# LO_synth_sma.net
KiCad netlist of a schematic drawn in EAGLE
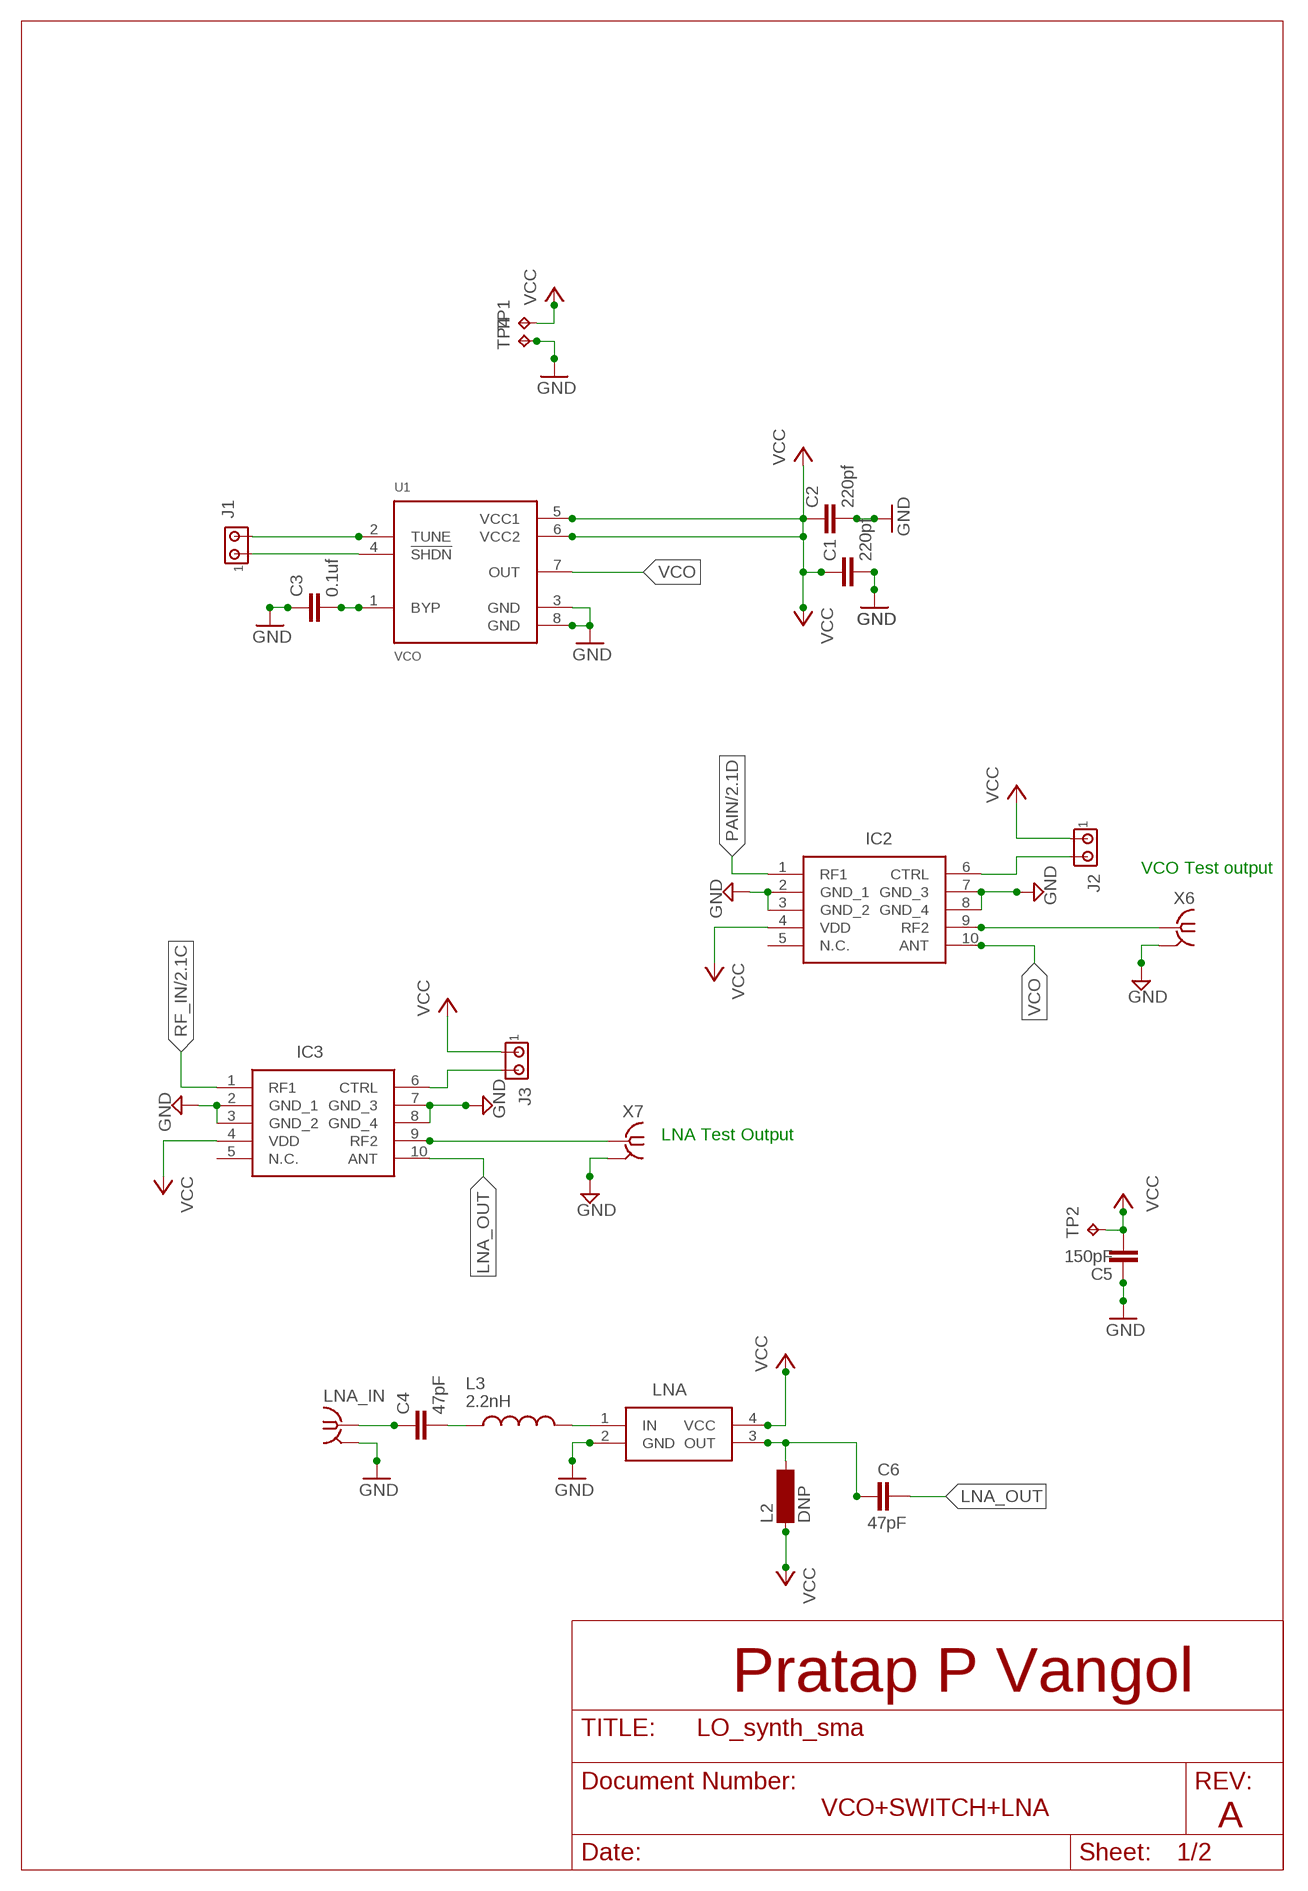
[diagram p0: schematic, sheet 1]
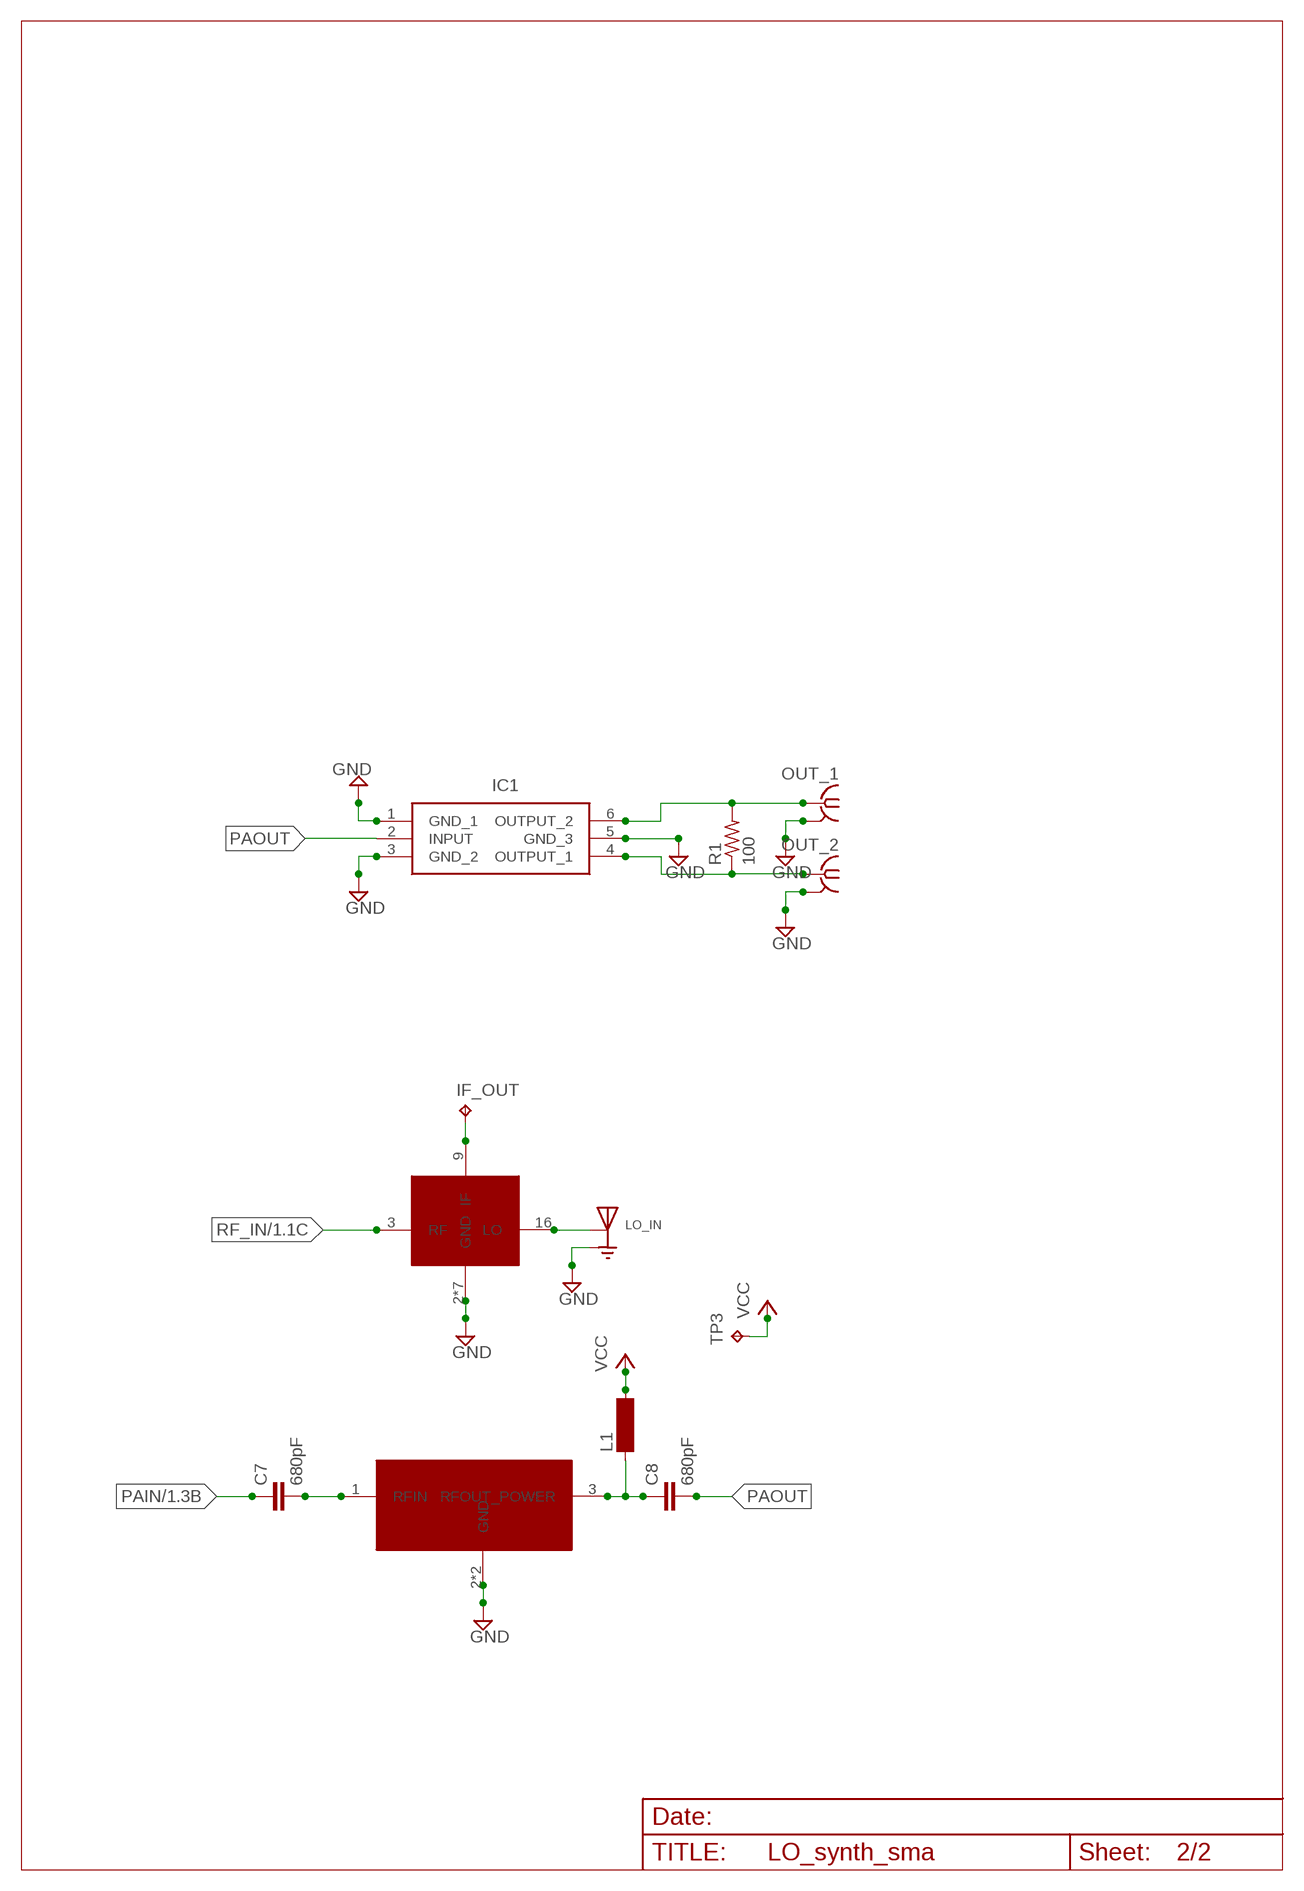
[diagram p1: schematic, sheet 2]

(export (version "E")
  (design (tool "Eeschema 10.0.6"))
  (components
    (comp (ref "C1")
      (value "220pf")
      (footprint "eagle-import:C0805")
      (libsource (lib "eagle-import") (part "C-EUC0805"))
    )
    (comp (ref "C2")
      (value "220pf")
      (footprint "eagle-import:C0805")
      (libsource (lib "eagle-import") (part "C-EUC0805"))
    )
    (comp (ref "C3")
      (value "0.1uf")
      (footprint "eagle-import:C0805")
      (libsource (lib "eagle-import") (part "C-EUC0805"))
    )
    (comp (ref "C4")
      (value "47pF")
      (footprint "eagle-import:C0805K")
      (libsource (lib "eagle-import") (part "C-EUC0805K"))
    )
    (comp (ref "C5")
      (value "150pF")
      (footprint "eagle-import:C0805K")
      (libsource (lib "eagle-import") (part "C-EUC0805K"))
    )
    (comp (ref "C6")
      (value "47pF")
      (footprint "eagle-import:C0805K")
      (libsource (lib "eagle-import") (part "C-EUC0805K"))
    )
    (comp (ref "IC2")
      (value "BGS12PN10E6327XTSA1")
      (footprint "eagle-import:BGSA11GN10E6327XTSA1")
      (fields (field (name "MOUSER_PART_NUMBER") "726-BGS12PN10E6327XT"))
      (libsource (lib "eagle-import") (part "BGS12PN10E6327XTSA1"))
    )
    (comp (ref "IC3")
      (value "BGS12PN10E6327XTSA1")
      (footprint "eagle-import:BGSA11GN10E6327XTSA1")
      (fields (field (name "MOUSER_PART_NUMBER") "726-BGS12PN10E6327XT"))
      (libsource (lib "eagle-import") (part "BGS12PN10E6327XTSA1"))
    )
    (comp (ref "J1")
      (value "MTA02-100")
      (footprint "eagle-import:10X02MTA")
      (libsource (lib "eagle-import") (part "MTA02-100"))
    )
    (comp (ref "J2")
      (value "MTA02-100")
      (footprint "eagle-import:10X02MTA")
      (fields (field (name "SPICEPREFIX") "B"))
      (libsource (lib "eagle-import") (part "MTA02-100"))
    )
    (comp (ref "J3")
      (value "MTA02-100")
      (footprint "eagle-import:10X02MTA")
      (fields (field (name "SPICEPREFIX") "B"))
      (libsource (lib "eagle-import") (part "MTA02-100"))
    )
    (comp (ref "L2")
      (value "DNP")
      (footprint "eagle-import:MS85")
      (libsource (lib "eagle-import") (part "MS85"))
    )
    (comp (ref "L3")
      (value "2.2nH")
      (footprint "eagle-import:INDC2012X103N")
      (fields (field (name "MF") "Bourns") (field (name "MP") "CE201210-2N2D"))
      (libsource (lib "eagle-import") (part "CE201210-2N2D"))
    )
    (comp (ref "LNA")
      (value "BGA622H6820XTSA1")
      (footprint "eagle-import:BGA622H6820XTSA1")
      (fields (field (name "MOUSER_PART_NUMBER") "726-BGA622H6820XTSA1"))
      (libsource (lib "eagle-import") (part "BGA622H6820XTSA1"))
    )
    (comp (ref "LNA_IN")
      (value "SMA-142-0711-821/826")
      (footprint "eagle-import:J502-ND-142-0711-821_826")
      (fields (field (name "MF") "JOHNSON COMPONENTS") (field (name "MPN") "142-0711-821"))
      (libsource (lib "eagle-import") (part "SMA-142-0711-821/826"))
    )
    (comp (ref "TP1")
      (value "TPPAD1-13")
      (footprint "eagle-import:P1-13")
      (libsource (lib "eagle-import") (part "TPPAD1-13"))
    )
    (comp (ref "TP2")
      (value "TPPAD1-13")
      (footprint "eagle-import:P1-13")
      (libsource (lib "eagle-import") (part "TPPAD1-13"))
    )
    (comp (ref "TP4")
      (value "TPPAD1-13")
      (footprint "eagle-import:P1-13")
      (libsource (lib "eagle-import") (part "TPPAD1-13"))
    )
    (comp (ref "U1")
      (value "VCO")
      (footprint "eagle-import:SOP65P490X110-8N")
      (fields (field (name "MF") "Maxim Integrated") (field (name "MP") "MAX2750EUA+"))
      (libsource (lib "eagle-import") (part "MAX2750EUA+"))
    )
    (comp (ref "X6")
      (value "VCO Test")
      (footprint "eagle-import:J502-ND-142-0711-821_826")
      (fields (field (name "MF") "JOHNSON COMPONENTS") (field (name "MPN") "142-0711-821"))
      (libsource (lib "eagle-import") (part "SMA-142-0711-821/826"))
    )
    (comp (ref "X7")
      (value "SMA-142-0711-821/826")
      (footprint "eagle-import:J502-ND-142-0711-821_826")
      (fields (field (name "MF") "JOHNSON COMPONENTS") (field (name "MPN") "142-0711-821"))
      (libsource (lib "eagle-import") (part "SMA-142-0711-821/826"))
    )
    (comp (ref "C7")
      (value "680pF")
      (footprint "eagle-import:C0805K")
      (libsource (lib "eagle-import") (part "C-EUC0805K"))
    )
    (comp (ref "C8")
      (value "680pF")
      (footprint "eagle-import:C0805K")
      (libsource (lib "eagle-import") (part "C-EUC0805K"))
    )
    (comp (ref "IC1")
      (value "PD2425J5050S2HF")
      (footprint "eagle-import:PD2425J5050S2HF")
      (fields (field (name "MOUSER_PART_NUMBER") "620-PD2425J5050S2HF"))
      (libsource (lib "eagle-import") (part "PD2425J5050S2HF"))
    )
    (comp (ref "IF_OUT")
      (value "TPPAD1-13")
      (footprint "eagle-import:P1-13")
      (libsource (lib "eagle-import") (part "TPPAD1-13"))
    )
    (comp (ref "L1")
      (value "MS85")
      (footprint "eagle-import:MS85")
      (libsource (lib "eagle-import") (part "MS85"))
    )
    (comp (ref "LO_IN")
      (value "U.FL-R-SMT-1(10)")
      (footprint "eagle-import:HRS_U.FL-R-SMT-1(10)")
      (fields (field (name "MF") "Hirose") (field (name "MP") "U.FL-R-SMT-1_10_"))
      (libsource (lib "eagle-import") (part "U.FL-R-SMT-1(10)"))
    )
    (comp (ref "OUT_1")
      (value "SMA-142-0711-821/826")
      (footprint "eagle-import:J502-ND-142-0711-821_826")
      (fields (field (name "MF") "JOHNSON COMPONENTS") (field (name "MPN") "142-0711-821"))
      (libsource (lib "eagle-import") (part "SMA-142-0711-821/826"))
    )
    (comp (ref "OUT_2")
      (value "SMA-142-0711-821/826")
      (footprint "eagle-import:J502-ND-142-0711-821_826")
      (fields (field (name "MF") "JOHNSON COMPONENTS") (field (name "MPN") "142-0711-821"))
      (libsource (lib "eagle-import") (part "SMA-142-0711-821/826"))
    )
    (comp (ref "R1")
      (value "100")
      (footprint "eagle-import:R0603")
      (libsource (lib "eagle-import") (part "R-US_R0603"))
    )
    (comp (ref "TP3")
      (value "TPPAD1-13")
      (footprint "eagle-import:P1-13")
      (libsource (lib "eagle-import") (part "TPPAD1-13"))
    )
    (comp (ref "U$1")
      (value "MDB-73H+QFN-24")
      (footprint "eagle-import:QFN24")
      (libsource (lib "eagle-import") (part "MDB-73H+QFN-24"))
    )
    (comp (ref "U$2")
      (value "GVA-60+")
      (footprint "eagle-import:SOT89")
      (libsource (lib "eagle-import") (part "GVA-60+"))
    )
  )
  (nets
    (net (code "1") (name "GND") (class "Default")
      (node (ref "C1") (pin "2") (pinfunction "2_2") (pintype "passive"))
      (node (ref "C2") (pin "2") (pinfunction "2_2") (pintype "passive"))
      (node (ref "C3") (pin "1") (pinfunction "1_1") (pintype "passive"))
      (node (ref "C5") (pin "1") (pinfunction "1_1") (pintype "passive"))
      (node (ref "IC1") (pin "1") (pinfunction "GND_1_1") (pintype "bidirectional"))
      (node (ref "IC1") (pin "3") (pinfunction "GND_2_3") (pintype "bidirectional"))
      (node (ref "IC1") (pin "5") (pinfunction "GND_3_5") (pintype "bidirectional"))
      (node (ref "IC2") (pin "2") (pinfunction "GND_1_2") (pintype "bidirectional"))
      (node (ref "IC2") (pin "3") (pinfunction "GND_2_3") (pintype "bidirectional"))
      (node (ref "IC2") (pin "7") (pinfunction "GND_3_7") (pintype "bidirectional"))
      (node (ref "IC2") (pin "8") (pinfunction "GND_4_8") (pintype "bidirectional"))
      (node (ref "IC3") (pin "2") (pinfunction "GND_1_2") (pintype "bidirectional"))
      (node (ref "IC3") (pin "3") (pinfunction "GND_2_3") (pintype "bidirectional"))
      (node (ref "IC3") (pin "7") (pinfunction "GND_3_7") (pintype "bidirectional"))
      (node (ref "IC3") (pin "8") (pinfunction "GND_4_8") (pintype "bidirectional"))
      (node (ref "LNA") (pin "2") (pinfunction "GND_2") (pintype "bidirectional"))
      (node (ref "LNA_IN") (pin "G@1") (pinfunction "2_G@1") (pintype "passive"))
      (node (ref "LNA_IN") (pin "G@2") (pinfunction "2_G@2") (pintype "passive"))
      (node (ref "LNA_IN") (pin "G@3") (pinfunction "2_G@3") (pintype "passive"))
      (node (ref "LNA_IN") (pin "G@4") (pinfunction "2_G@4") (pintype "passive"))
      (node (ref "LO_IN") (pin "1") (pinfunction "GND_1") (pintype "passive"))
      (node (ref "LO_IN") (pin "3") (pinfunction "GND_3") (pintype "passive"))
      (node (ref "OUT_1") (pin "G@1") (pinfunction "2_G@1") (pintype "passive"))
      (node (ref "OUT_1") (pin "G@2") (pinfunction "2_G@2") (pintype "passive"))
      (node (ref "OUT_1") (pin "G@3") (pinfunction "2_G@3") (pintype "passive"))
      (node (ref "OUT_1") (pin "G@4") (pinfunction "2_G@4") (pintype "passive"))
      (node (ref "OUT_2") (pin "G@1") (pinfunction "2_G@1") (pintype "passive"))
      (node (ref "OUT_2") (pin "G@2") (pinfunction "2_G@2") (pintype "passive"))
      (node (ref "OUT_2") (pin "G@3") (pinfunction "2_G@3") (pintype "passive"))
      (node (ref "OUT_2") (pin "G@4") (pinfunction "2_G@4") (pintype "passive"))
      (node (ref "TP4") (pin "TP") (pinfunction "TP_TP") (pintype "input"))
      (node (ref "U$1") (pin "10") (pinfunction "GND_10") (pintype "bidirectional"))
      (node (ref "U$1") (pin "15") (pinfunction "GND_15") (pintype "bidirectional"))
      (node (ref "U$1") (pin "17") (pinfunction "GND_17") (pintype "bidirectional"))
      (node (ref "U$1") (pin "2") (pinfunction "GND_2") (pintype "bidirectional"))
      (node (ref "U$1") (pin "4") (pinfunction "GND_4") (pintype "bidirectional"))
      (node (ref "U$1") (pin "8") (pinfunction "GND_8") (pintype "bidirectional"))
      (node (ref "U$1") (pin "PD") (pinfunction "GND_PD") (pintype "bidirectional"))
      (node (ref "U$2") (pin "2") (pinfunction "GND_2") (pintype "power_in"))
      (node (ref "U$2") (pin "2@1") (pinfunction "GND_2@1") (pintype "power_in"))
      (node (ref "U1") (pin "3") (pinfunction "GND_3") (pintype "power_in"))
      (node (ref "U1") (pin "8") (pinfunction "GND_8") (pintype "power_in"))
      (node (ref "X6") (pin "G@1") (pinfunction "2_G@1") (pintype "passive"))
      (node (ref "X6") (pin "G@2") (pinfunction "2_G@2") (pintype "passive"))
      (node (ref "X6") (pin "G@3") (pinfunction "2_G@3") (pintype "passive"))
      (node (ref "X6") (pin "G@4") (pinfunction "2_G@4") (pintype "passive"))
      (node (ref "X7") (pin "G@1") (pinfunction "2_G@1") (pintype "passive"))
      (node (ref "X7") (pin "G@2") (pinfunction "2_G@2") (pintype "passive"))
      (node (ref "X7") (pin "G@3") (pinfunction "2_G@3") (pintype "passive"))
      (node (ref "X7") (pin "G@4") (pinfunction "2_G@4") (pintype "passive"))
    )
    (net (code "2") (name "LNA_OUT") (class "Default")
      (node (ref "C6") (pin "2") (pinfunction "2_2") (pintype "passive"))
      (node (ref "IC3") (pin "10") (pinfunction "ANT_10") (pintype "bidirectional"))
    )
    (net (code "3") (name "Net-(C4-Pad1)") (class "Default")
      (node (ref "C4") (pin "1") (pinfunction "1_1") (pintype "passive"))
      (node (ref "LNA_IN") (pin "1") (pinfunction "1_1") (pintype "passive"))
    )
    (net (code "4") (name "Net-(C4-Pad2)") (class "Default")
      (node (ref "C4") (pin "2") (pinfunction "2_2") (pintype "passive"))
      (node (ref "L3") (pin "1") (pinfunction "1_1") (pintype "passive"))
    )
    (net (code "5") (name "Net-(IC1-OUTPUT_1)") (class "Default")
      (node (ref "IC1") (pin "4") (pinfunction "OUTPUT_1_4") (pintype "bidirectional"))
      (node (ref "OUT_2") (pin "1") (pinfunction "1_1") (pintype "passive"))
      (node (ref "R1") (pin "1") (pinfunction "1_1") (pintype "passive"))
    )
    (net (code "6") (name "Net-(IC1-OUTPUT_2)") (class "Default")
      (node (ref "IC1") (pin "6") (pinfunction "OUTPUT_2_6") (pintype "bidirectional"))
      (node (ref "OUT_1") (pin "1") (pinfunction "1_1") (pintype "passive"))
      (node (ref "R1") (pin "2") (pinfunction "2_2") (pintype "passive"))
    )
    (net (code "7") (name "Net-(IC2-CTRL)") (class "Default")
      (node (ref "IC2") (pin "6") (pinfunction "CTRL_6") (pintype "bidirectional"))
      (node (ref "J2") (pin "2") (pinfunction "2_2") (pintype "passive"))
    )
    (net (code "8") (name "Net-(IC2-RF2)") (class "Default")
      (node (ref "IC2") (pin "9") (pinfunction "RF2_9") (pintype "bidirectional"))
      (node (ref "X6") (pin "1") (pinfunction "1_1") (pintype "passive"))
    )
    (net (code "9") (name "Net-(IC3-CTRL)") (class "Default")
      (node (ref "IC3") (pin "6") (pinfunction "CTRL_6") (pintype "bidirectional"))
      (node (ref "J3") (pin "2") (pinfunction "2_2") (pintype "passive"))
    )
    (net (code "10") (name "Net-(IC3-RF2)") (class "Default")
      (node (ref "IC3") (pin "9") (pinfunction "RF2_9") (pintype "bidirectional"))
      (node (ref "X7") (pin "1") (pinfunction "1_1") (pintype "passive"))
    )
    (net (code "11") (name "Net-(LNA-IN)") (class "Default")
      (node (ref "L3") (pin "2") (pinfunction "2_2") (pintype "passive"))
      (node (ref "LNA") (pin "1") (pinfunction "IN_1") (pintype "bidirectional"))
    )
    (net (code "12") (name "Net-(LNA-OUT)") (class "Default")
      (node (ref "C6") (pin "1") (pinfunction "1_1") (pintype "passive"))
      (node (ref "L2") (pin "2") (pinfunction "2_2") (pintype "passive"))
      (node (ref "LNA") (pin "3") (pinfunction "OUT_3") (pintype "bidirectional"))
    )
    (net (code "13") (name "Net-(LO_IN-SIG)") (class "Default")
      (node (ref "LO_IN") (pin "2") (pinfunction "SIG_2") (pintype "passive"))
      (node (ref "U$1") (pin "16") (pinfunction "LO_16") (pintype "bidirectional"))
    )
    (net (code "14") (name "Net-(U$1-IF)") (class "Default")
      (node (ref "IF_OUT") (pin "TP") (pinfunction "TP_TP") (pintype "input"))
      (node (ref "U$1") (pin "9") (pinfunction "IF_9") (pintype "bidirectional"))
    )
    (net (code "15") (name "Net-(U$2-RFIN)") (class "Default")
      (node (ref "C7") (pin "2") (pinfunction "2_2") (pintype "passive"))
      (node (ref "U$2") (pin "1") (pinfunction "RFIN_1") (pintype "input"))
    )
    (net (code "16") (name "Net-(U$2-RFOUT_POWER)") (class "Default")
      (node (ref "C8") (pin "1") (pinfunction "1_1") (pintype "passive"))
      (node (ref "L1") (pin "1") (pinfunction "1_1") (pintype "passive"))
      (node (ref "U$2") (pin "3") (pinfunction "RFOUT_POWER_3") (pintype "output"))
    )
    (net (code "17") (name "Net-(U1-BYP)") (class "Default")
      (node (ref "C3") (pin "2") (pinfunction "2_2") (pintype "passive"))
      (node (ref "U1") (pin "1") (pinfunction "BYP_1") (pintype "passive"))
    )
    (net (code "18") (name "Net-(U1-TUNE)") (class "Default")
      (node (ref "J1") (pin "2") (pinfunction "2_2") (pintype "passive"))
      (node (ref "U1") (pin "2") (pinfunction "TUNE_2") (pintype "input"))
    )
    (net (code "19") (name "Net-(U1-~{SHDN})") (class "Default")
      (node (ref "J1") (pin "1") (pinfunction "1_1") (pintype "passive"))
      (node (ref "U1") (pin "4") (pinfunction "~{SHDN}_4") (pintype "input"))
    )
    (net (code "20") (name "PAIN") (class "Default")
      (node (ref "C7") (pin "1") (pinfunction "1_1") (pintype "passive"))
      (node (ref "IC2") (pin "1") (pinfunction "RF1_1") (pintype "bidirectional"))
    )
    (net (code "21") (name "PAOUT") (class "Default")
      (node (ref "C8") (pin "2") (pinfunction "2_2") (pintype "passive"))
      (node (ref "IC1") (pin "2") (pinfunction "INPUT_2") (pintype "bidirectional"))
    )
    (net (code "22") (name "RF_IN") (class "Default")
      (node (ref "IC3") (pin "1") (pinfunction "RF1_1") (pintype "bidirectional"))
      (node (ref "U$1") (pin "3") (pinfunction "RF_3") (pintype "bidirectional"))
    )
    (net (code "23") (name "VCC") (class "Default")
      (node (ref "C1") (pin "1") (pinfunction "1_1") (pintype "passive"))
      (node (ref "C2") (pin "1") (pinfunction "1_1") (pintype "passive"))
      (node (ref "C5") (pin "2") (pinfunction "2_2") (pintype "passive"))
      (node (ref "IC2") (pin "4") (pinfunction "VDD_4") (pintype "bidirectional"))
      (node (ref "IC3") (pin "4") (pinfunction "VDD_4") (pintype "bidirectional"))
      (node (ref "J2") (pin "1") (pinfunction "1_1") (pintype "passive"))
      (node (ref "J3") (pin "1") (pinfunction "1_1") (pintype "passive"))
      (node (ref "L1") (pin "2") (pinfunction "2_2") (pintype "passive"))
      (node (ref "L2") (pin "1") (pinfunction "1_1") (pintype "passive"))
      (node (ref "LNA") (pin "4") (pinfunction "VCC_4") (pintype "bidirectional"))
      (node (ref "TP1") (pin "TP") (pinfunction "TP_TP") (pintype "input"))
      (node (ref "TP2") (pin "TP") (pinfunction "TP_TP") (pintype "input"))
      (node (ref "TP3") (pin "TP") (pinfunction "TP_TP") (pintype "input"))
      (node (ref "U1") (pin "5") (pinfunction "VCC1_5") (pintype "power_in"))
      (node (ref "U1") (pin "6") (pinfunction "VCC2_6") (pintype "power_in"))
    )
    (net (code "24") (name "VCO") (class "Default")
      (node (ref "IC2") (pin "10") (pinfunction "ANT_10") (pintype "bidirectional"))
      (node (ref "U1") (pin "7") (pinfunction "OUT_7") (pintype "output"))
    )
    (net (code "25") (name "unconnected-(IC2-N.C.-Pad5)") (class "Default")
      (node (ref "IC2") (pin "5") (pinfunction "N.C._5") (pintype "no_connect"))
    )
    (net (code "26") (name "unconnected-(IC3-N.C.-Pad5)") (class "Default")
      (node (ref "IC3") (pin "5") (pinfunction "N.C._5") (pintype "no_connect"))
    )
  )
)
